# InputBlock.net
KiCad netlist of a schematic drawn in EAGLE
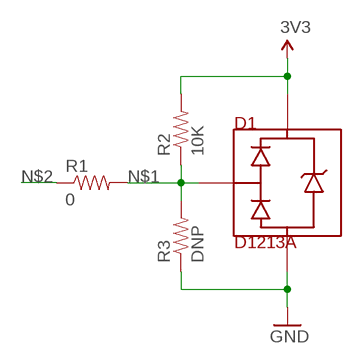
[diagram p0: schematic, sheet 1]

(export (version "E")
  (design (tool "Eeschema 10.0.6"))
  (components
    (comp (ref "D1")
      (value "D1213A")
      (footprint "eagle-import:DLP")
      (libsource (lib "eagle-import") (part "D1213A-DLP"))
    )
    (comp (ref "R1")
      (value "0")
      (footprint "eagle-import:0603-RES")
      (libsource (lib "eagle-import") (part "RES-0-0603"))
    )
    (comp (ref "R2")
      (value "10K")
      (footprint "eagle-import:0603-RES")
      (libsource (lib "eagle-import") (part "RES-10K-06030603"))
    )
    (comp (ref "R3")
      (value "DNP")
      (footprint "eagle-import:0603-RES")
      (libsource (lib "eagle-import") (part "RES-DNP-0603"))
    )
  )
  (nets
    (net (code "1") (name "/N$1") (class "Default")
      (node (ref "D1") (pin "SIGNAL") (pinfunction "SIGNAL_SIGNAL") (pintype "bidirectional"))
      (node (ref "R1") (pin "2") (pinfunction "2_2") (pintype "passive"))
      (node (ref "R2") (pin "1") (pinfunction "1_1") (pintype "passive"))
      (node (ref "R3") (pin "2") (pinfunction "2_2") (pintype "passive"))
    )
    (net (code "2") (name "/N$2") (class "Default")
      (node (ref "R1") (pin "1") (pinfunction "1_1") (pintype "passive"))
    )
    (net (code "3") (name "3V3") (class "Default")
      (node (ref "D1") (pin "VCC") (pinfunction "VCC_VCC") (pintype "power_in"))
      (node (ref "R2") (pin "2") (pinfunction "2_2") (pintype "passive"))
    )
    (net (code "4") (name "GND") (class "Default")
      (node (ref "D1") (pin "GND") (pinfunction "GND_GND") (pintype "power_in"))
      (node (ref "R3") (pin "1") (pinfunction "1_1") (pintype "passive"))
    )
  )
)
